# R603D.net
KiCad netlist of a schematic drawn in EAGLE
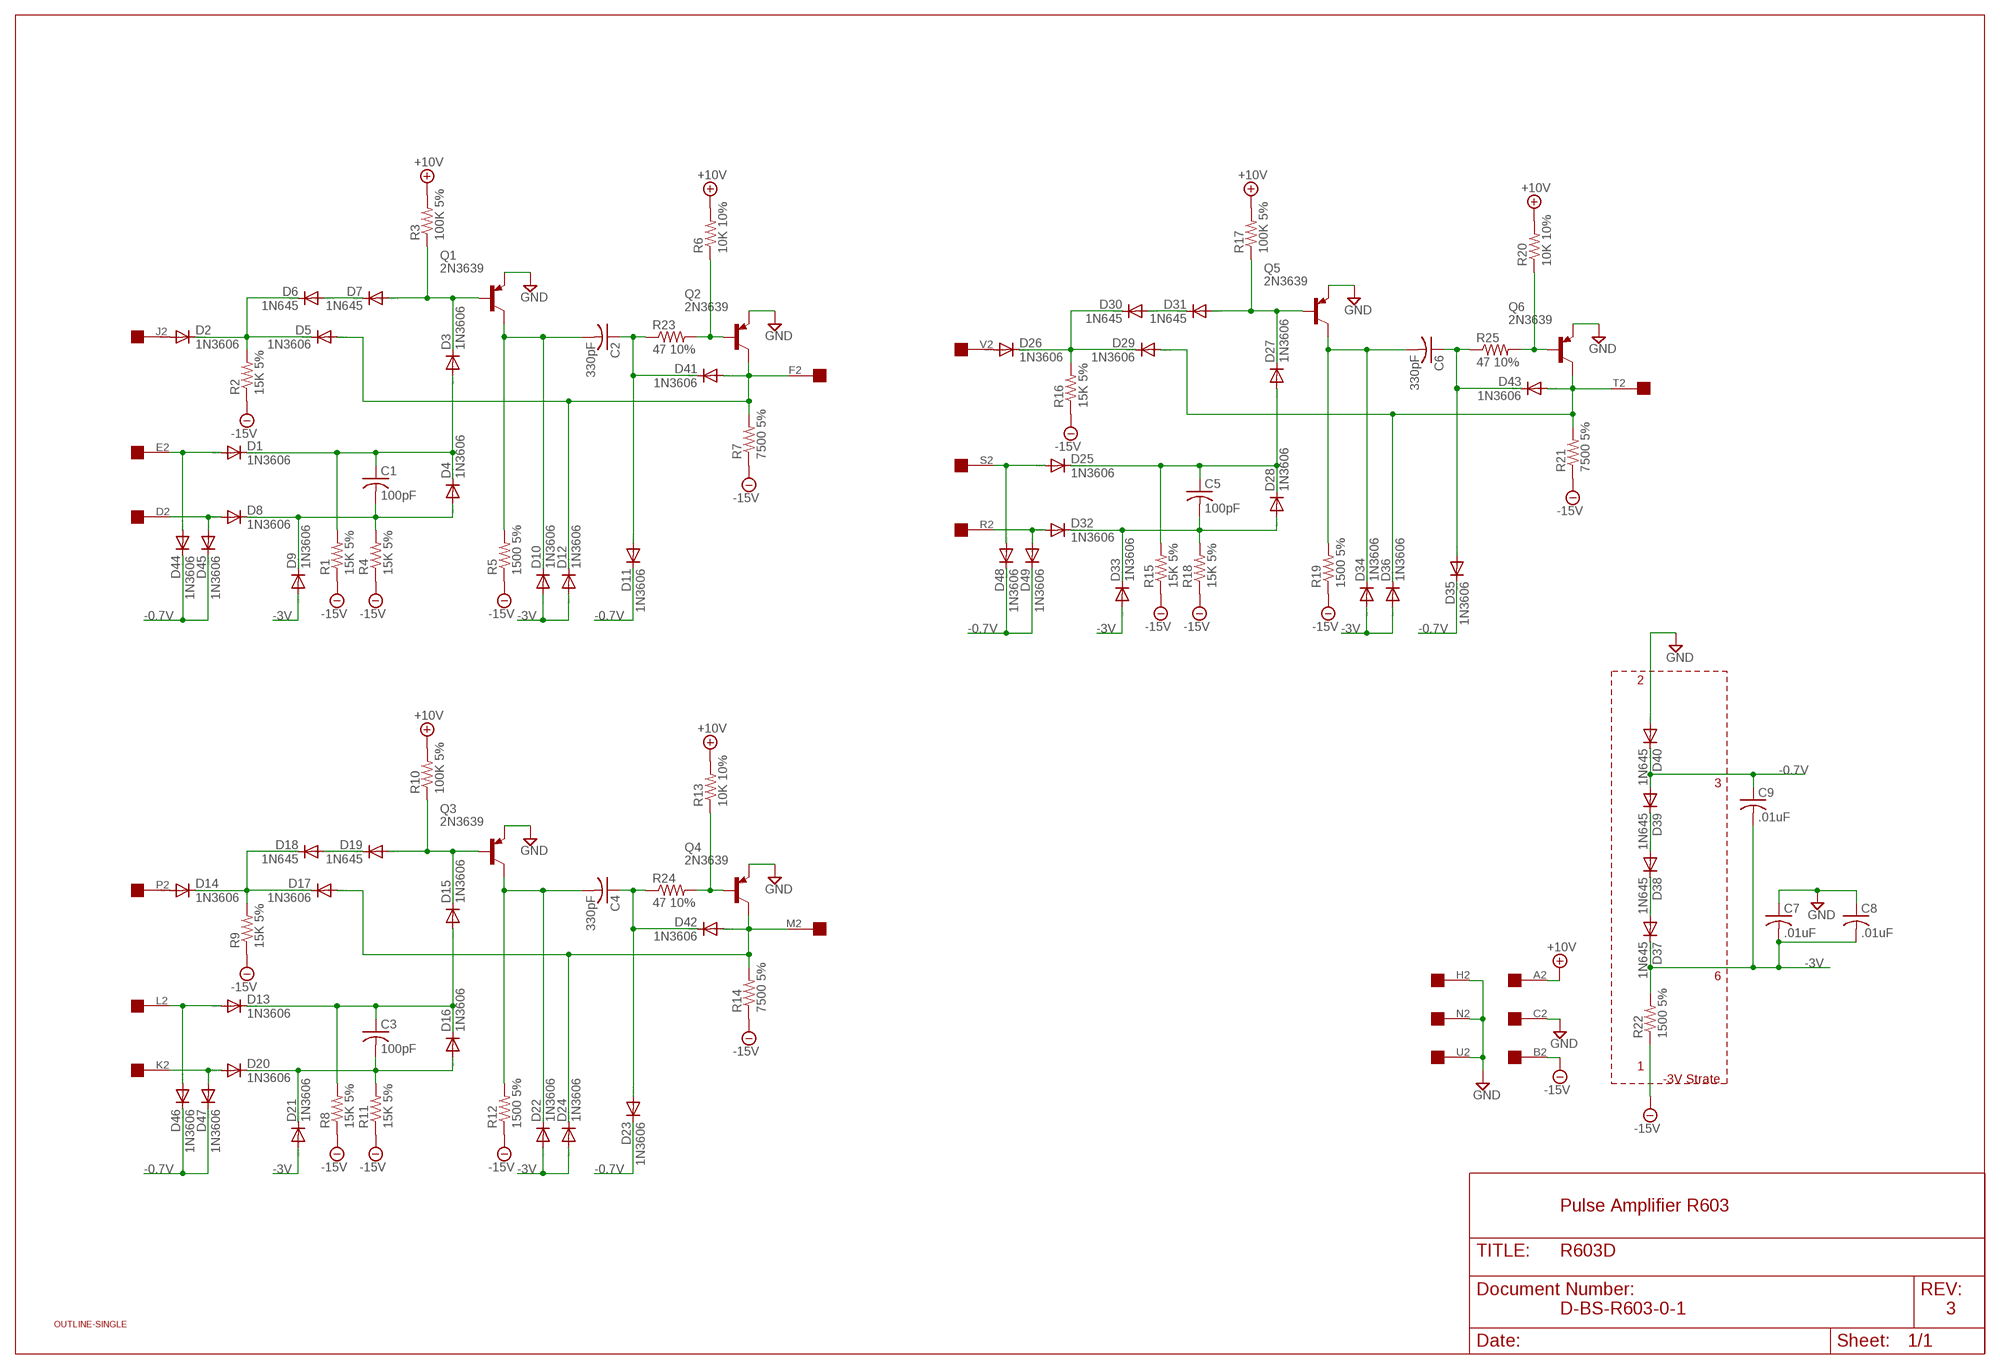
[diagram p0: schematic, sheet 1]

(export (version "E")
  (design (tool "Eeschema 10.0.6"))
  (components
    (comp (ref "C1")
      (value "100pF")
      (footprint "eagle-import:C050-025X075")
      (libsource (lib "eagle-import") (part "C-US050-025X075"))
    )
    (comp (ref "C2")
      (value "330pF")
      (footprint "eagle-import:C050-025X075")
      (libsource (lib "eagle-import") (part "C-US050-025X075"))
    )
    (comp (ref "C3")
      (value "100pF")
      (footprint "eagle-import:C050-025X075")
      (libsource (lib "eagle-import") (part "C-US050-025X075"))
    )
    (comp (ref "C4")
      (value "330pF")
      (footprint "eagle-import:C050-025X075")
      (libsource (lib "eagle-import") (part "C-US050-025X075"))
    )
    (comp (ref "C5")
      (value "100pF")
      (footprint "eagle-import:C050-025X075")
      (libsource (lib "eagle-import") (part "C-US050-025X075"))
    )
    (comp (ref "C6")
      (value "330pF")
      (footprint "eagle-import:C050-025X075")
      (libsource (lib "eagle-import") (part "C-US050-025X075"))
    )
    (comp (ref "C7")
      (value ".01uF")
      (footprint "eagle-import:C050-025X075")
      (libsource (lib "eagle-import") (part "C-US050-025X075"))
    )
    (comp (ref "C8")
      (value ".01uF")
      (footprint "eagle-import:C050-025X075")
      (libsource (lib "eagle-import") (part "C-US050-025X075"))
    )
    (comp (ref "C9")
      (value ".01uF")
      (footprint "eagle-import:C050-025X075")
      (libsource (lib "eagle-import") (part "C-US050-025X075"))
    )
    (comp (ref "D1")
      (value "1N3606")
      (footprint "eagle-import:DO35-10")
      (libsource (lib "eagle-import") (part "1N4148DO35-10"))
    )
    (comp (ref "D2")
      (value "1N3606")
      (footprint "eagle-import:DO35-10")
      (libsource (lib "eagle-import") (part "1N4148DO35-10"))
    )
    (comp (ref "D3")
      (value "1N3606")
      (footprint "eagle-import:DO35-10")
      (libsource (lib "eagle-import") (part "1N4148DO35-10"))
    )
    (comp (ref "D4")
      (value "1N3606")
      (footprint "eagle-import:DO35-10")
      (libsource (lib "eagle-import") (part "1N4148DO35-10"))
    )
    (comp (ref "D5")
      (value "1N3606")
      (footprint "eagle-import:DO35-10")
      (libsource (lib "eagle-import") (part "1N4148DO35-10"))
    )
    (comp (ref "D6")
      (value "1N645")
      (footprint "eagle-import:DO35-10")
      (libsource (lib "eagle-import") (part "1N4148DO35-10"))
    )
    (comp (ref "D7")
      (value "1N645")
      (footprint "eagle-import:DO35-10")
      (libsource (lib "eagle-import") (part "1N4148DO35-10"))
    )
    (comp (ref "D8")
      (value "1N3606")
      (footprint "eagle-import:DO35-10")
      (libsource (lib "eagle-import") (part "1N4148DO35-10"))
    )
    (comp (ref "D9")
      (value "1N3606")
      (footprint "eagle-import:DO35-10")
      (libsource (lib "eagle-import") (part "1N4148DO35-10"))
    )
    (comp (ref "D10")
      (value "1N3606")
      (footprint "eagle-import:DO35-10")
      (libsource (lib "eagle-import") (part "1N4148DO35-10"))
    )
    (comp (ref "D11")
      (value "1N3606")
      (footprint "eagle-import:DO35-10")
      (libsource (lib "eagle-import") (part "1N4148DO35-10"))
    )
    (comp (ref "D12")
      (value "1N3606")
      (footprint "eagle-import:DO35-10")
      (libsource (lib "eagle-import") (part "1N4148DO35-10"))
    )
    (comp (ref "D13")
      (value "1N3606")
      (footprint "eagle-import:DO35-10")
      (libsource (lib "eagle-import") (part "1N4148DO35-10"))
    )
    (comp (ref "D14")
      (value "1N3606")
      (footprint "eagle-import:DO35-10")
      (libsource (lib "eagle-import") (part "1N4148DO35-10"))
    )
    (comp (ref "D15")
      (value "1N3606")
      (footprint "eagle-import:DO35-10")
      (libsource (lib "eagle-import") (part "1N4148DO35-10"))
    )
    (comp (ref "D16")
      (value "1N3606")
      (footprint "eagle-import:DO35-10")
      (libsource (lib "eagle-import") (part "1N4148DO35-10"))
    )
    (comp (ref "D17")
      (value "1N3606")
      (footprint "eagle-import:DO35-10")
      (libsource (lib "eagle-import") (part "1N4148DO35-10"))
    )
    (comp (ref "D18")
      (value "1N645")
      (footprint "eagle-import:DO35-10")
      (libsource (lib "eagle-import") (part "1N4148DO35-10"))
    )
    (comp (ref "D19")
      (value "1N645")
      (footprint "eagle-import:DO35-10")
      (libsource (lib "eagle-import") (part "1N4148DO35-10"))
    )
    (comp (ref "D20")
      (value "1N3606")
      (footprint "eagle-import:DO35-10")
      (libsource (lib "eagle-import") (part "1N4148DO35-10"))
    )
    (comp (ref "D21")
      (value "1N3606")
      (footprint "eagle-import:DO35-10")
      (libsource (lib "eagle-import") (part "1N4148DO35-10"))
    )
    (comp (ref "D22")
      (value "1N3606")
      (footprint "eagle-import:DO35-10")
      (libsource (lib "eagle-import") (part "1N4148DO35-10"))
    )
    (comp (ref "D23")
      (value "1N3606")
      (footprint "eagle-import:DO35-10")
      (libsource (lib "eagle-import") (part "1N4148DO35-10"))
    )
    (comp (ref "D24")
      (value "1N3606")
      (footprint "eagle-import:DO35-10")
      (libsource (lib "eagle-import") (part "1N4148DO35-10"))
    )
    (comp (ref "D25")
      (value "1N3606")
      (footprint "eagle-import:DO35-10")
      (libsource (lib "eagle-import") (part "1N4148DO35-10"))
    )
    (comp (ref "D26")
      (value "1N3606")
      (footprint "eagle-import:DO35-10")
      (libsource (lib "eagle-import") (part "1N4148DO35-10"))
    )
    (comp (ref "D27")
      (value "1N3606")
      (footprint "eagle-import:DO35-10")
      (libsource (lib "eagle-import") (part "1N4148DO35-10"))
    )
    (comp (ref "D28")
      (value "1N3606")
      (footprint "eagle-import:DO35-10")
      (libsource (lib "eagle-import") (part "1N4148DO35-10"))
    )
    (comp (ref "D29")
      (value "1N3606")
      (footprint "eagle-import:DO35-10")
      (libsource (lib "eagle-import") (part "1N4148DO35-10"))
    )
    (comp (ref "D30")
      (value "1N645")
      (footprint "eagle-import:DO35-10")
      (libsource (lib "eagle-import") (part "1N4148DO35-10"))
    )
    (comp (ref "D31")
      (value "1N645")
      (footprint "eagle-import:DO35-10")
      (libsource (lib "eagle-import") (part "1N4148DO35-10"))
    )
    (comp (ref "D32")
      (value "1N3606")
      (footprint "eagle-import:DO35-10")
      (libsource (lib "eagle-import") (part "1N4148DO35-10"))
    )
    (comp (ref "D33")
      (value "1N3606")
      (footprint "eagle-import:DO35-10")
      (libsource (lib "eagle-import") (part "1N4148DO35-10"))
    )
    (comp (ref "D34")
      (value "1N3606")
      (footprint "eagle-import:DO35-10")
      (libsource (lib "eagle-import") (part "1N4148DO35-10"))
    )
    (comp (ref "D35")
      (value "1N3606")
      (footprint "eagle-import:DO35-10")
      (libsource (lib "eagle-import") (part "1N4148DO35-10"))
    )
    (comp (ref "D36")
      (value "1N3606")
      (footprint "eagle-import:DO35-10")
      (libsource (lib "eagle-import") (part "1N4148DO35-10"))
    )
    (comp (ref "D37")
      (value "1N645")
      (footprint "eagle-import:DO35-10")
      (libsource (lib "eagle-import") (part "1N4148DO35-10"))
    )
    (comp (ref "D38")
      (value "1N645")
      (footprint "eagle-import:DO35-10")
      (libsource (lib "eagle-import") (part "1N4148DO35-10"))
    )
    (comp (ref "D39")
      (value "1N645")
      (footprint "eagle-import:DO35-10")
      (libsource (lib "eagle-import") (part "1N4148DO35-10"))
    )
    (comp (ref "D40")
      (value "1N645")
      (footprint "eagle-import:DO35-10")
      (libsource (lib "eagle-import") (part "1N4148DO35-10"))
    )
    (comp (ref "D41")
      (value "1N3606")
      (footprint "eagle-import:DO35-10")
      (libsource (lib "eagle-import") (part "1N4148DO35-10"))
    )
    (comp (ref "D42")
      (value "1N3606")
      (footprint "eagle-import:DO35-10")
      (libsource (lib "eagle-import") (part "1N4148DO35-10"))
    )
    (comp (ref "D43")
      (value "1N3606")
      (footprint "eagle-import:DO35-10")
      (libsource (lib "eagle-import") (part "1N4148DO35-10"))
    )
    (comp (ref "D44")
      (value "1N3606")
      (footprint "eagle-import:DO35-10")
      (libsource (lib "eagle-import") (part "1N4148DO35-10"))
    )
    (comp (ref "D45")
      (value "1N3606")
      (footprint "eagle-import:DO35-10")
      (libsource (lib "eagle-import") (part "1N4148DO35-10"))
    )
    (comp (ref "D46")
      (value "1N3606")
      (footprint "eagle-import:DO35-10")
      (libsource (lib "eagle-import") (part "1N4148DO35-10"))
    )
    (comp (ref "D47")
      (value "1N3606")
      (footprint "eagle-import:DO35-10")
      (libsource (lib "eagle-import") (part "1N4148DO35-10"))
    )
    (comp (ref "D48")
      (value "1N3606")
      (footprint "eagle-import:DO35-10")
      (libsource (lib "eagle-import") (part "1N4148DO35-10"))
    )
    (comp (ref "D49")
      (value "1N3606")
      (footprint "eagle-import:DO35-10")
      (libsource (lib "eagle-import") (part "1N4148DO35-10"))
    )
    (comp (ref "Q1")
      (value "2N3639")
      (footprint "eagle-import:TO39")
      (libsource (lib "eagle-import") (part "2N2904"))
    )
    (comp (ref "Q2")
      (value "2N3639")
      (footprint "eagle-import:TO39")
      (libsource (lib "eagle-import") (part "2N2904"))
    )
    (comp (ref "Q3")
      (value "2N3639")
      (footprint "eagle-import:TO39")
      (libsource (lib "eagle-import") (part "2N2904"))
    )
    (comp (ref "Q4")
      (value "2N3639")
      (footprint "eagle-import:TO39")
      (libsource (lib "eagle-import") (part "2N2904"))
    )
    (comp (ref "Q5")
      (value "2N3639")
      (footprint "eagle-import:TO39")
      (libsource (lib "eagle-import") (part "2N2904"))
    )
    (comp (ref "Q6")
      (value "2N3639")
      (footprint "eagle-import:TO39")
      (libsource (lib "eagle-import") (part "2N2904"))
    )
    (comp (ref "R1")
      (value "15K 5%")
      (footprint "eagle-import:0207_10")
      (libsource (lib "eagle-import") (part "R-US_0207/10"))
    )
    (comp (ref "R2")
      (value "15K 5%")
      (footprint "eagle-import:0207_10")
      (libsource (lib "eagle-import") (part "R-US_0207/10"))
    )
    (comp (ref "R3")
      (value "100K 5%")
      (footprint "eagle-import:0207_10")
      (libsource (lib "eagle-import") (part "R-US_0207/10"))
    )
    (comp (ref "R4")
      (value "15K 5%")
      (footprint "eagle-import:0207_10")
      (libsource (lib "eagle-import") (part "R-US_0207/10"))
    )
    (comp (ref "R5")
      (value "1500 5%")
      (footprint "eagle-import:0207_10")
      (libsource (lib "eagle-import") (part "R-US_0207/10"))
    )
    (comp (ref "R6")
      (value "10K 10%")
      (footprint "eagle-import:0207_10")
      (libsource (lib "eagle-import") (part "R-US_0207/10"))
    )
    (comp (ref "R7")
      (value "7500 5%")
      (footprint "eagle-import:0207_10")
      (libsource (lib "eagle-import") (part "R-US_0207/10"))
    )
    (comp (ref "R8")
      (value "15K 5%")
      (footprint "eagle-import:0207_10")
      (libsource (lib "eagle-import") (part "R-US_0207/10"))
    )
    (comp (ref "R9")
      (value "15K 5%")
      (footprint "eagle-import:0207_10")
      (libsource (lib "eagle-import") (part "R-US_0207/10"))
    )
    (comp (ref "R10")
      (value "100K 5%")
      (footprint "eagle-import:0207_10")
      (libsource (lib "eagle-import") (part "R-US_0207/10"))
    )
    (comp (ref "R11")
      (value "15K 5%")
      (footprint "eagle-import:0207_10")
      (libsource (lib "eagle-import") (part "R-US_0207/10"))
    )
    (comp (ref "R12")
      (value "1500 5%")
      (footprint "eagle-import:0207_10")
      (libsource (lib "eagle-import") (part "R-US_0207/10"))
    )
    (comp (ref "R13")
      (value "10K 10%")
      (footprint "eagle-import:0207_10")
      (libsource (lib "eagle-import") (part "R-US_0207/10"))
    )
    (comp (ref "R14")
      (value "7500 5%")
      (footprint "eagle-import:0207_10")
      (libsource (lib "eagle-import") (part "R-US_0207/10"))
    )
    (comp (ref "R15")
      (value "15K 5%")
      (footprint "eagle-import:0207_10")
      (libsource (lib "eagle-import") (part "R-US_0207/10"))
    )
    (comp (ref "R16")
      (value "15K 5%")
      (footprint "eagle-import:0207_10")
      (libsource (lib "eagle-import") (part "R-US_0207/10"))
    )
    (comp (ref "R17")
      (value "100K 5%")
      (footprint "eagle-import:0207_10")
      (libsource (lib "eagle-import") (part "R-US_0207/10"))
    )
    (comp (ref "R18")
      (value "15K 5%")
      (footprint "eagle-import:0207_10")
      (libsource (lib "eagle-import") (part "R-US_0207/10"))
    )
    (comp (ref "R19")
      (value "1500 5%")
      (footprint "eagle-import:0207_10")
      (libsource (lib "eagle-import") (part "R-US_0207/10"))
    )
    (comp (ref "R20")
      (value "10K 10%")
      (footprint "eagle-import:0207_10")
      (libsource (lib "eagle-import") (part "R-US_0207/10"))
    )
    (comp (ref "R21")
      (value "7500 5%")
      (footprint "eagle-import:0207_10")
      (libsource (lib "eagle-import") (part "R-US_0207/10"))
    )
    (comp (ref "R22")
      (value "1500 5%")
      (footprint "eagle-import:0207_10")
      (libsource (lib "eagle-import") (part "R-US_0207/10"))
    )
    (comp (ref "R23")
      (value "47 10%")
      (footprint "eagle-import:0207_10")
      (libsource (lib "eagle-import") (part "R-US_0207/10"))
    )
    (comp (ref "R24")
      (value "47 10%")
      (footprint "eagle-import:0207_10")
      (libsource (lib "eagle-import") (part "R-US_0207/10"))
    )
    (comp (ref "R25")
      (value "47 10%")
      (footprint "eagle-import:0207_10")
      (libsource (lib "eagle-import") (part "R-US_0207/10"))
    )
    (comp (ref "U$1")
      (value "OUTLINE-SINGLE")
      (footprint "eagle-import:SINGLE")
      (libsource (lib "eagle-import") (part "OUTLINE-SINGLE"))
    )
    (comp (ref "U$2")
      (value "EDGE-1")
      (footprint "eagle-import:EDGE-CON1")
      (libsource (lib "eagle-import") (part "EDGE-1"))
    )
  )
  (nets
    (net (code "1") (name "+10V") (class "Default")
      (node (ref "R10") (pin "2") (pinfunction "2_2") (pintype "passive"))
      (node (ref "R13") (pin "2") (pinfunction "2_2") (pintype "passive"))
      (node (ref "R17") (pin "2") (pinfunction "2_2") (pintype "passive"))
      (node (ref "R20") (pin "2") (pinfunction "2_2") (pintype "passive"))
      (node (ref "R3") (pin "2") (pinfunction "2_2") (pintype "passive"))
      (node (ref "R6") (pin "2") (pinfunction "2_2") (pintype "passive"))
      (node (ref "U$2") (pin "A2") (pinfunction "1_A2") (pintype "bidirectional"))
    )
    (net (code "2") (name "-15V") (class "Default")
      (node (ref "R1") (pin "1") (pinfunction "1_1") (pintype "passive"))
      (node (ref "R11") (pin "1") (pinfunction "1_1") (pintype "passive"))
      (node (ref "R12") (pin "1") (pinfunction "1_1") (pintype "passive"))
      (node (ref "R14") (pin "1") (pinfunction "1_1") (pintype "passive"))
      (node (ref "R15") (pin "1") (pinfunction "1_1") (pintype "passive"))
      (node (ref "R16") (pin "1") (pinfunction "1_1") (pintype "passive"))
      (node (ref "R18") (pin "1") (pinfunction "1_1") (pintype "passive"))
      (node (ref "R19") (pin "1") (pinfunction "1_1") (pintype "passive"))
      (node (ref "R2") (pin "1") (pinfunction "1_1") (pintype "passive"))
      (node (ref "R21") (pin "1") (pinfunction "1_1") (pintype "passive"))
      (node (ref "R22") (pin "1") (pinfunction "1_1") (pintype "passive"))
      (node (ref "R4") (pin "1") (pinfunction "1_1") (pintype "passive"))
      (node (ref "R5") (pin "1") (pinfunction "1_1") (pintype "passive"))
      (node (ref "R7") (pin "1") (pinfunction "1_1") (pintype "passive"))
      (node (ref "R8") (pin "1") (pinfunction "1_1") (pintype "passive"))
      (node (ref "R9") (pin "1") (pinfunction "1_1") (pintype "passive"))
      (node (ref "U$2") (pin "B2") (pinfunction "1_B2") (pintype "bidirectional"))
    )
    (net (code "3") (name "/-0.7V") (class "Default")
      (node (ref "C9") (pin "1") (pinfunction "1_1") (pintype "passive"))
      (node (ref "D11") (pin "C") (pinfunction "C_C") (pintype "passive"))
      (node (ref "D23") (pin "C") (pinfunction "C_C") (pintype "passive"))
      (node (ref "D35") (pin "C") (pinfunction "C_C") (pintype "passive"))
      (node (ref "D39") (pin "A") (pinfunction "A_A") (pintype "passive"))
      (node (ref "D40") (pin "C") (pinfunction "C_C") (pintype "passive"))
      (node (ref "D44") (pin "C") (pinfunction "C_C") (pintype "passive"))
      (node (ref "D45") (pin "C") (pinfunction "C_C") (pintype "passive"))
      (node (ref "D46") (pin "C") (pinfunction "C_C") (pintype "passive"))
      (node (ref "D47") (pin "C") (pinfunction "C_C") (pintype "passive"))
      (node (ref "D48") (pin "C") (pinfunction "C_C") (pintype "passive"))
      (node (ref "D49") (pin "C") (pinfunction "C_C") (pintype "passive"))
    )
    (net (code "4") (name "/-3V") (class "Default")
      (node (ref "C7") (pin "2") (pinfunction "2_2") (pintype "passive"))
      (node (ref "C8") (pin "2") (pinfunction "2_2") (pintype "passive"))
      (node (ref "C9") (pin "2") (pinfunction "2_2") (pintype "passive"))
      (node (ref "D10") (pin "A") (pinfunction "A_A") (pintype "passive"))
      (node (ref "D12") (pin "A") (pinfunction "A_A") (pintype "passive"))
      (node (ref "D21") (pin "A") (pinfunction "A_A") (pintype "passive"))
      (node (ref "D22") (pin "A") (pinfunction "A_A") (pintype "passive"))
      (node (ref "D24") (pin "A") (pinfunction "A_A") (pintype "passive"))
      (node (ref "D33") (pin "A") (pinfunction "A_A") (pintype "passive"))
      (node (ref "D34") (pin "A") (pinfunction "A_A") (pintype "passive"))
      (node (ref "D36") (pin "A") (pinfunction "A_A") (pintype "passive"))
      (node (ref "D37") (pin "C") (pinfunction "C_C") (pintype "passive"))
      (node (ref "D9") (pin "A") (pinfunction "A_A") (pintype "passive"))
      (node (ref "R22") (pin "2") (pinfunction "2_2") (pintype "passive"))
    )
    (net (code "5") (name "GND") (class "Default")
      (node (ref "C7") (pin "1") (pinfunction "1_1") (pintype "passive"))
      (node (ref "C8") (pin "1") (pinfunction "1_1") (pintype "passive"))
      (node (ref "D40") (pin "A") (pinfunction "A_A") (pintype "passive"))
      (node (ref "Q1") (pin "1") (pinfunction "E_1") (pintype "passive"))
      (node (ref "Q2") (pin "1") (pinfunction "E_1") (pintype "passive"))
      (node (ref "Q3") (pin "1") (pinfunction "E_1") (pintype "passive"))
      (node (ref "Q4") (pin "1") (pinfunction "E_1") (pintype "passive"))
      (node (ref "Q5") (pin "1") (pinfunction "E_1") (pintype "passive"))
      (node (ref "Q6") (pin "1") (pinfunction "E_1") (pintype "passive"))
      (node (ref "U$2") (pin "C2") (pinfunction "1_C2") (pintype "bidirectional"))
      (node (ref "U$2") (pin "H2") (pinfunction "1_H2") (pintype "bidirectional"))
      (node (ref "U$2") (pin "N2") (pinfunction "1_N2") (pintype "bidirectional"))
      (node (ref "U$2") (pin "U2") (pinfunction "1_U2") (pintype "bidirectional"))
    )
    (net (code "6") (name "Net-(C1-Pad1)") (class "Default")
      (node (ref "C1") (pin "1") (pinfunction "1_1") (pintype "passive"))
      (node (ref "D1") (pin "C") (pinfunction "C_C") (pintype "passive"))
      (node (ref "D3") (pin "A") (pinfunction "A_A") (pintype "passive"))
      (node (ref "D4") (pin "C") (pinfunction "C_C") (pintype "passive"))
      (node (ref "R1") (pin "2") (pinfunction "2_2") (pintype "passive"))
    )
    (net (code "7") (name "Net-(C1-Pad2)") (class "Default")
      (node (ref "C1") (pin "2") (pinfunction "2_2") (pintype "passive"))
      (node (ref "D4") (pin "A") (pinfunction "A_A") (pintype "passive"))
      (node (ref "D8") (pin "C") (pinfunction "C_C") (pintype "passive"))
      (node (ref "D9") (pin "C") (pinfunction "C_C") (pintype "passive"))
      (node (ref "R4") (pin "2") (pinfunction "2_2") (pintype "passive"))
    )
    (net (code "8") (name "Net-(C2-Pad1)") (class "Default")
      (node (ref "C2") (pin "1") (pinfunction "1_1") (pintype "passive"))
      (node (ref "D11") (pin "A") (pinfunction "A_A") (pintype "passive"))
      (node (ref "D41") (pin "C") (pinfunction "C_C") (pintype "passive"))
      (node (ref "R23") (pin "1") (pinfunction "1_1") (pintype "passive"))
    )
    (net (code "9") (name "Net-(C3-Pad1)") (class "Default")
      (node (ref "C3") (pin "1") (pinfunction "1_1") (pintype "passive"))
      (node (ref "D13") (pin "C") (pinfunction "C_C") (pintype "passive"))
      (node (ref "D15") (pin "A") (pinfunction "A_A") (pintype "passive"))
      (node (ref "D16") (pin "C") (pinfunction "C_C") (pintype "passive"))
      (node (ref "R8") (pin "2") (pinfunction "2_2") (pintype "passive"))
    )
    (net (code "10") (name "Net-(C3-Pad2)") (class "Default")
      (node (ref "C3") (pin "2") (pinfunction "2_2") (pintype "passive"))
      (node (ref "D16") (pin "A") (pinfunction "A_A") (pintype "passive"))
      (node (ref "D20") (pin "C") (pinfunction "C_C") (pintype "passive"))
      (node (ref "D21") (pin "C") (pinfunction "C_C") (pintype "passive"))
      (node (ref "R11") (pin "2") (pinfunction "2_2") (pintype "passive"))
    )
    (net (code "11") (name "Net-(C4-Pad1)") (class "Default")
      (node (ref "C4") (pin "1") (pinfunction "1_1") (pintype "passive"))
      (node (ref "D23") (pin "A") (pinfunction "A_A") (pintype "passive"))
      (node (ref "D42") (pin "C") (pinfunction "C_C") (pintype "passive"))
      (node (ref "R24") (pin "1") (pinfunction "1_1") (pintype "passive"))
    )
    (net (code "12") (name "Net-(C5-Pad1)") (class "Default")
      (node (ref "C5") (pin "1") (pinfunction "1_1") (pintype "passive"))
      (node (ref "D25") (pin "C") (pinfunction "C_C") (pintype "passive"))
      (node (ref "D27") (pin "A") (pinfunction "A_A") (pintype "passive"))
      (node (ref "D28") (pin "C") (pinfunction "C_C") (pintype "passive"))
      (node (ref "R15") (pin "2") (pinfunction "2_2") (pintype "passive"))
    )
    (net (code "13") (name "Net-(C5-Pad2)") (class "Default")
      (node (ref "C5") (pin "2") (pinfunction "2_2") (pintype "passive"))
      (node (ref "D28") (pin "A") (pinfunction "A_A") (pintype "passive"))
      (node (ref "D32") (pin "C") (pinfunction "C_C") (pintype "passive"))
      (node (ref "D33") (pin "C") (pinfunction "C_C") (pintype "passive"))
      (node (ref "R18") (pin "2") (pinfunction "2_2") (pintype "passive"))
    )
    (net (code "14") (name "Net-(C6-Pad1)") (class "Default")
      (node (ref "C6") (pin "1") (pinfunction "1_1") (pintype "passive"))
      (node (ref "D35") (pin "A") (pinfunction "A_A") (pintype "passive"))
      (node (ref "D43") (pin "C") (pinfunction "C_C") (pintype "passive"))
      (node (ref "R25") (pin "1") (pinfunction "1_1") (pintype "passive"))
    )
    (net (code "15") (name "Net-(D2-PadC)") (class "Default")
      (node (ref "D2") (pin "C") (pinfunction "C_C") (pintype "passive"))
      (node (ref "D5") (pin "C") (pinfunction "C_C") (pintype "passive"))
      (node (ref "D6") (pin "C") (pinfunction "C_C") (pintype "passive"))
      (node (ref "R2") (pin "2") (pinfunction "2_2") (pintype "passive"))
    )
    (net (code "16") (name "Net-(D6-PadA)") (class "Default")
      (node (ref "D6") (pin "A") (pinfunction "A_A") (pintype "passive"))
      (node (ref "D7") (pin "C") (pinfunction "C_C") (pintype "passive"))
    )
    (net (code "17") (name "Net-(D14-PadC)") (class "Default")
      (node (ref "D14") (pin "C") (pinfunction "C_C") (pintype "passive"))
      (node (ref "D17") (pin "C") (pinfunction "C_C") (pintype "passive"))
      (node (ref "D18") (pin "C") (pinfunction "C_C") (pintype "passive"))
      (node (ref "R9") (pin "2") (pinfunction "2_2") (pintype "passive"))
    )
    (net (code "18") (name "Net-(D18-PadA)") (class "Default")
      (node (ref "D18") (pin "A") (pinfunction "A_A") (pintype "passive"))
      (node (ref "D19") (pin "C") (pinfunction "C_C") (pintype "passive"))
    )
    (net (code "19") (name "Net-(D26-PadC)") (class "Default")
      (node (ref "D26") (pin "C") (pinfunction "C_C") (pintype "passive"))
      (node (ref "D29") (pin "C") (pinfunction "C_C") (pintype "passive"))
      (node (ref "D30") (pin "C") (pinfunction "C_C") (pintype "passive"))
      (node (ref "R16") (pin "2") (pinfunction "2_2") (pintype "passive"))
    )
    (net (code "20") (name "Net-(D30-PadA)") (class "Default")
      (node (ref "D30") (pin "A") (pinfunction "A_A") (pintype "passive"))
      (node (ref "D31") (pin "C") (pinfunction "C_C") (pintype "passive"))
    )
    (net (code "21") (name "Net-(D37-PadA)") (class "Default")
      (node (ref "D37") (pin "A") (pinfunction "A_A") (pintype "passive"))
      (node (ref "D38") (pin "C") (pinfunction "C_C") (pintype "passive"))
    )
    (net (code "22") (name "Net-(D38-PadA)") (class "Default")
      (node (ref "D38") (pin "A") (pinfunction "A_A") (pintype "passive"))
      (node (ref "D39") (pin "C") (pinfunction "C_C") (pintype "passive"))
    )
    (net (code "23") (name "Net-(Q1-B)") (class "Default")
      (node (ref "D3") (pin "C") (pinfunction "C_C") (pintype "passive"))
      (node (ref "D7") (pin "A") (pinfunction "A_A") (pintype "passive"))
      (node (ref "Q1") (pin "2") (pinfunction "B_2") (pintype "passive"))
      (node (ref "R3") (pin "1") (pinfunction "1_1") (pintype "passive"))
    )
    (net (code "24") (name "Net-(Q1-C)") (class "Default")
      (node (ref "C2") (pin "2") (pinfunction "2_2") (pintype "passive"))
      (node (ref "D10") (pin "C") (pinfunction "C_C") (pintype "passive"))
      (node (ref "Q1") (pin "3") (pinfunction "C_3") (pintype "passive"))
      (node (ref "R5") (pin "2") (pinfunction "2_2") (pintype "passive"))
    )
    (net (code "25") (name "Net-(Q2-B)") (class "Default")
      (node (ref "Q2") (pin "2") (pinfunction "B_2") (pintype "passive"))
      (node (ref "R23") (pin "2") (pinfunction "2_2") (pintype "passive"))
      (node (ref "R6") (pin "1") (pinfunction "1_1") (pintype "passive"))
    )
    (net (code "26") (name "Net-(Q2-C)") (class "Default")
      (node (ref "D12") (pin "C") (pinfunction "C_C") (pintype "passive"))
      (node (ref "D41") (pin "A") (pinfunction "A_A") (pintype "passive"))
      (node (ref "D5") (pin "A") (pinfunction "A_A") (pintype "passive"))
      (node (ref "Q2") (pin "3") (pinfunction "C_3") (pintype "passive"))
      (node (ref "R7") (pin "2") (pinfunction "2_2") (pintype "passive"))
      (node (ref "U$2") (pin "F2") (pinfunction "1_F2") (pintype "bidirectional"))
    )
    (net (code "27") (name "Net-(Q3-B)") (class "Default")
      (node (ref "D15") (pin "C") (pinfunction "C_C") (pintype "passive"))
      (node (ref "D19") (pin "A") (pinfunction "A_A") (pintype "passive"))
      (node (ref "Q3") (pin "2") (pinfunction "B_2") (pintype "passive"))
      (node (ref "R10") (pin "1") (pinfunction "1_1") (pintype "passive"))
    )
    (net (code "28") (name "Net-(Q3-C)") (class "Default")
      (node (ref "C4") (pin "2") (pinfunction "2_2") (pintype "passive"))
      (node (ref "D22") (pin "C") (pinfunction "C_C") (pintype "passive"))
      (node (ref "Q3") (pin "3") (pinfunction "C_3") (pintype "passive"))
      (node (ref "R12") (pin "2") (pinfunction "2_2") (pintype "passive"))
    )
    (net (code "29") (name "Net-(Q4-B)") (class "Default")
      (node (ref "Q4") (pin "2") (pinfunction "B_2") (pintype "passive"))
      (node (ref "R13") (pin "1") (pinfunction "1_1") (pintype "passive"))
      (node (ref "R24") (pin "2") (pinfunction "2_2") (pintype "passive"))
    )
    (net (code "30") (name "Net-(Q4-C)") (class "Default")
      (node (ref "D17") (pin "A") (pinfunction "A_A") (pintype "passive"))
      (node (ref "D24") (pin "C") (pinfunction "C_C") (pintype "passive"))
      (node (ref "D42") (pin "A") (pinfunction "A_A") (pintype "passive"))
      (node (ref "Q4") (pin "3") (pinfunction "C_3") (pintype "passive"))
      (node (ref "R14") (pin "2") (pinfunction "2_2") (pintype "passive"))
      (node (ref "U$2") (pin "M2") (pinfunction "1_M2") (pintype "bidirectional"))
    )
    (net (code "31") (name "Net-(Q5-B)") (class "Default")
      (node (ref "D27") (pin "C") (pinfunction "C_C") (pintype "passive"))
      (node (ref "D31") (pin "A") (pinfunction "A_A") (pintype "passive"))
      (node (ref "Q5") (pin "2") (pinfunction "B_2") (pintype "passive"))
      (node (ref "R17") (pin "1") (pinfunction "1_1") (pintype "passive"))
    )
    (net (code "32") (name "Net-(Q5-C)") (class "Default")
      (node (ref "C6") (pin "2") (pinfunction "2_2") (pintype "passive"))
      (node (ref "D34") (pin "C") (pinfunction "C_C") (pintype "passive"))
      (node (ref "Q5") (pin "3") (pinfunction "C_3") (pintype "passive"))
      (node (ref "R19") (pin "2") (pinfunction "2_2") (pintype "passive"))
    )
    (net (code "33") (name "Net-(Q6-B)") (class "Default")
      (node (ref "Q6") (pin "2") (pinfunction "B_2") (pintype "passive"))
      (node (ref "R20") (pin "1") (pinfunction "1_1") (pintype "passive"))
      (node (ref "R25") (pin "2") (pinfunction "2_2") (pintype "passive"))
    )
    (net (code "34") (name "Net-(Q6-C)") (class "Default")
      (node (ref "D29") (pin "A") (pinfunction "A_A") (pintype "passive"))
      (node (ref "D36") (pin "C") (pinfunction "C_C") (pintype "passive"))
      (node (ref "D43") (pin "A") (pinfunction "A_A") (pintype "passive"))
      (node (ref "Q6") (pin "3") (pinfunction "C_3") (pintype "passive"))
      (node (ref "R21") (pin "2") (pinfunction "2_2") (pintype "passive"))
      (node (ref "U$2") (pin "T2") (pinfunction "1_T2") (pintype "bidirectional"))
    )
    (net (code "35") (name "Net-(U$2D-1)") (class "Default")
      (node (ref "D45") (pin "A") (pinfunction "A_A") (pintype "passive"))
      (node (ref "D8") (pin "A") (pinfunction "A_A") (pintype "passive"))
      (node (ref "U$2") (pin "D2") (pinfunction "1_D2") (pintype "bidirectional"))
    )
    (net (code "36") (name "Net-(U$2E-1)") (class "Default")
      (node (ref "D1") (pin "A") (pinfunction "A_A") (pintype "passive"))
      (node (ref "D44") (pin "A") (pinfunction "A_A") (pintype "passive"))
      (node (ref "U$2") (pin "E2") (pinfunction "1_E2") (pintype "bidirectional"))
    )
    (net (code "37") (name "Net-(U$2H-1)") (class "Default")
      (node (ref "D2") (pin "A") (pinfunction "A_A") (pintype "passive"))
      (node (ref "U$2") (pin "J2") (pinfunction "1_J2") (pintype "bidirectional"))
    )
    (net (code "38") (name "Net-(U$2I-1)") (class "Default")
      (node (ref "D20") (pin "A") (pinfunction "A_A") (pintype "passive"))
      (node (ref "D47") (pin "A") (pinfunction "A_A") (pintype "passive"))
      (node (ref "U$2") (pin "K2") (pinfunction "1_K2") (pintype "bidirectional"))
    )
    (net (code "39") (name "Net-(U$2J-1)") (class "Default")
      (node (ref "D13") (pin "A") (pinfunction "A_A") (pintype "passive"))
      (node (ref "D46") (pin "A") (pinfunction "A_A") (pintype "passive"))
      (node (ref "U$2") (pin "L2") (pinfunction "1_L2") (pintype "bidirectional"))
    )
    (net (code "40") (name "Net-(U$2M-1)") (class "Default")
      (node (ref "D14") (pin "A") (pinfunction "A_A") (pintype "passive"))
      (node (ref "U$2") (pin "P2") (pinfunction "1_P2") (pintype "bidirectional"))
    )
    (net (code "41") (name "Net-(U$2N-1)") (class "Default")
      (node (ref "D32") (pin "A") (pinfunction "A_A") (pintype "passive"))
      (node (ref "D49") (pin "A") (pinfunction "A_A") (pintype "passive"))
      (node (ref "U$2") (pin "R2") (pinfunction "1_R2") (pintype "bidirectional"))
    )
    (net (code "42") (name "Net-(U$2O-1)") (class "Default")
      (node (ref "D25") (pin "A") (pinfunction "A_A") (pintype "passive"))
      (node (ref "D48") (pin "A") (pinfunction "A_A") (pintype "passive"))
      (node (ref "U$2") (pin "S2") (pinfunction "1_S2") (pintype "bidirectional"))
    )
    (net (code "43") (name "Net-(U$2R-1)") (class "Default")
      (node (ref "D26") (pin "A") (pinfunction "A_A") (pintype "passive"))
      (node (ref "U$2") (pin "V2") (pinfunction "1_V2") (pintype "bidirectional"))
    )
  )
)
